# LEDDriver.net
KiCad netlist of a schematic drawn in EAGLE
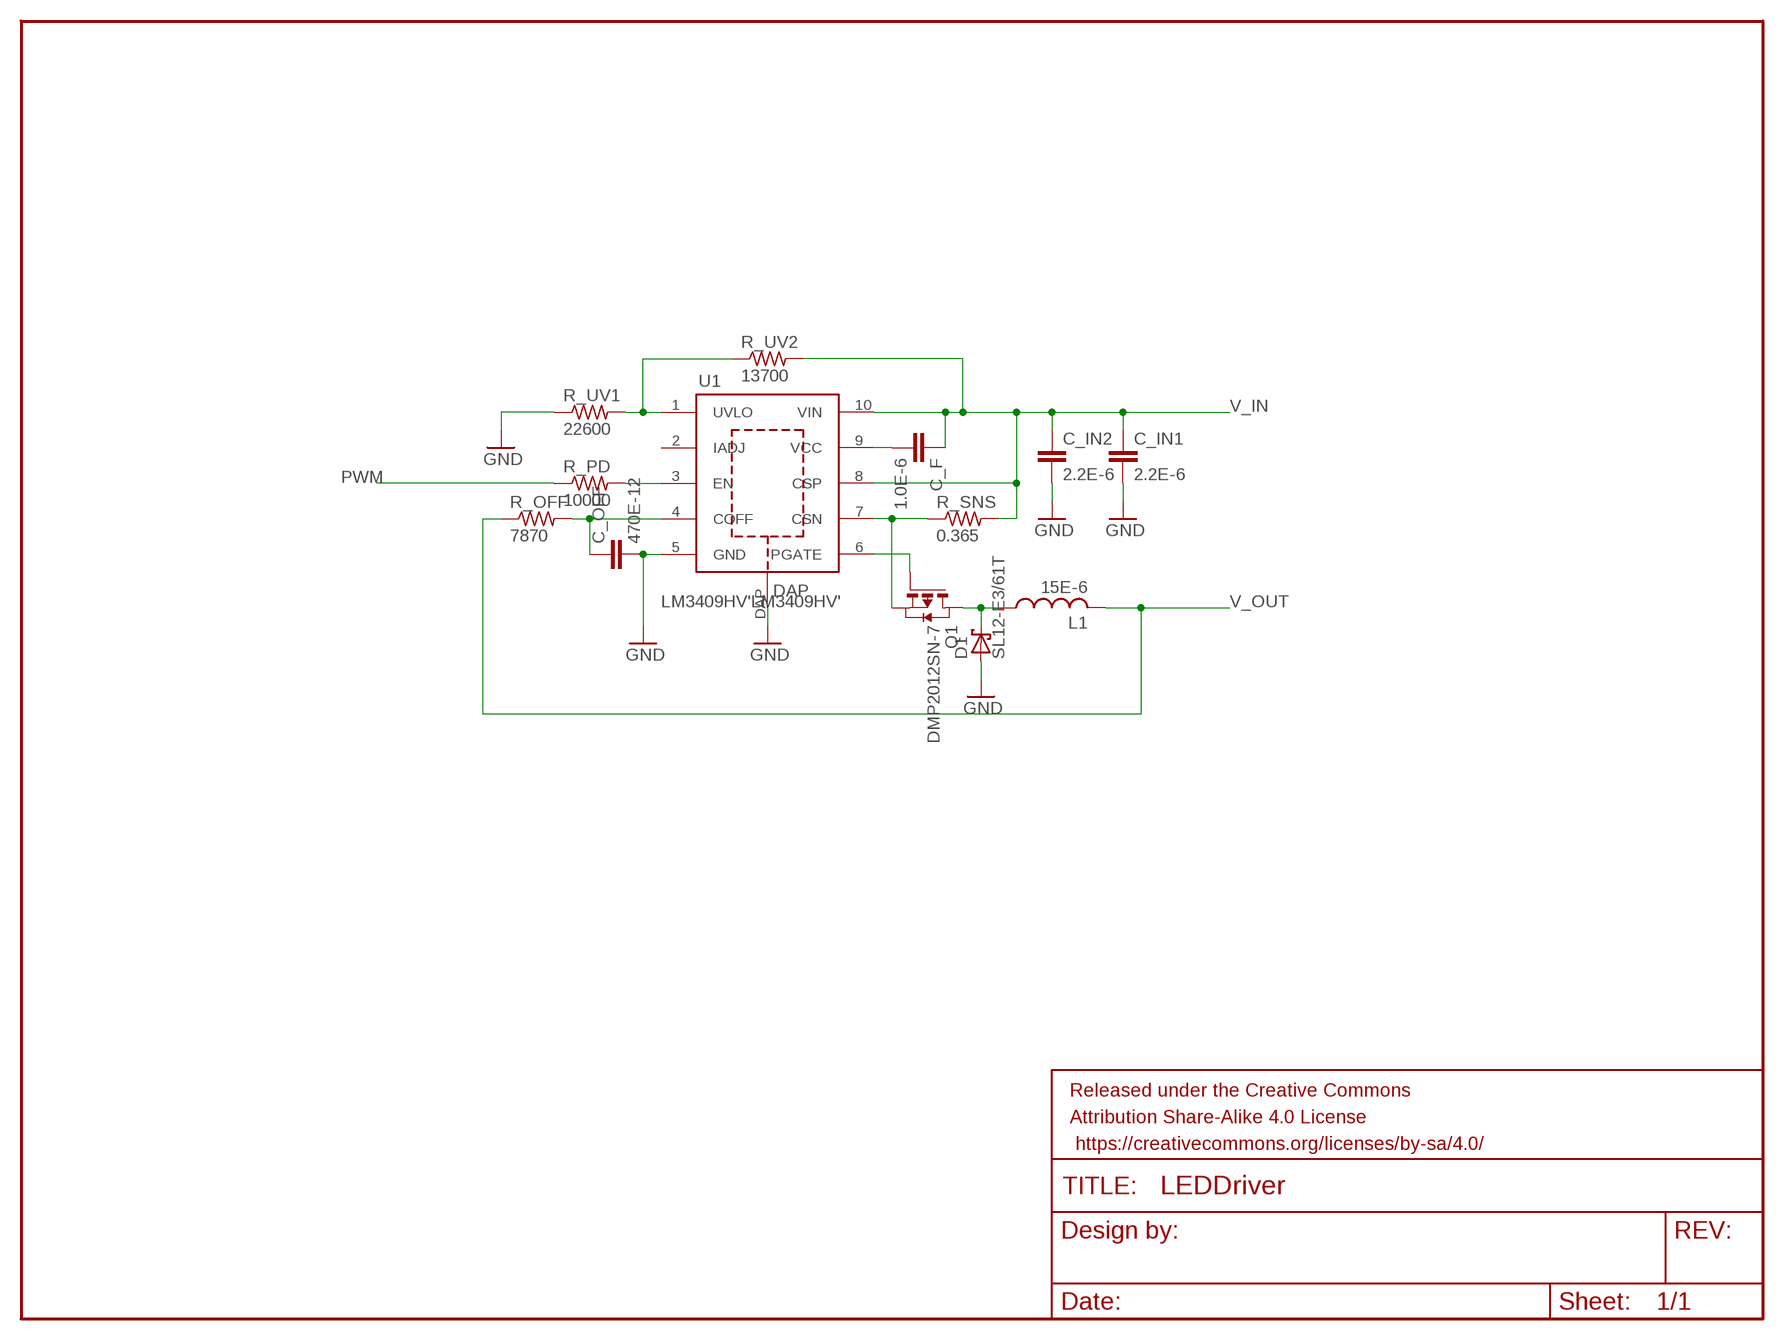
[diagram p0: schematic, sheet 1]

(export (version "E")
  (design (tool "Eeschema 10.0.6"))
  (components
    (comp (ref "C_F")
      (value "1.0E-6")
      (footprint "eagle-import:C0603")
      (libsource (lib "eagle-import") (part "CC0603"))
    )
    (comp (ref "C_IN1")
      (value "2.2E-6")
      (footprint "eagle-import:C0603")
      (libsource (lib "eagle-import") (part "CC0603"))
    )
    (comp (ref "C_IN2")
      (value "2.2E-6")
      (footprint "eagle-import:C0603")
      (libsource (lib "eagle-import") (part "CC0603"))
    )
    (comp (ref "C_OFF")
      (value "470E-12")
      (footprint "eagle-import:C0402")
      (libsource (lib "eagle-import") (part "CC0402"))
    )
    (comp (ref "D1")
      (value "SL12-E3/61T")
      (footprint "eagle-import:SL12-E3_61T")
      (libsource (lib "eagle-import") (part "SL12-E3/61T"))
    )
    (comp (ref "FRAME1")
      (value "FRAME-LETTER")
      (footprint "eagle-import:CREATIVE_COMMONS")
      (libsource (lib "eagle-import") (part "FRAME-LETTER"))
    )
    (comp (ref "L1")
      (value "15E-6")
      (footprint "eagle-import:SRN8040")
      (libsource (lib "eagle-import") (part "SRN8040"))
    )
    (comp (ref "Q1")
      (value "DMP2012SN-7")
      (footprint "eagle-import:DMP2012SN-7")
      (libsource (lib "eagle-import") (part "DMP2012SN-7"))
    )
    (comp (ref "R_OFF")
      (value "7870")
      (footprint "eagle-import:R0603")
      (libsource (lib "eagle-import") (part "R-US_R0603"))
    )
    (comp (ref "R_PD")
      (value "10000")
      (footprint "eagle-import:R0603")
      (libsource (lib "eagle-import") (part "R-US_R0603"))
    )
    (comp (ref "R_SNS")
      (value "0.365")
      (footprint "eagle-import:R2512")
      (libsource (lib "eagle-import") (part "R-US_R2512"))
    )
    (comp (ref "R_UV1")
      (value "22600")
      (footprint "eagle-import:R0603")
      (libsource (lib "eagle-import") (part "R-US_R0603"))
    )
    (comp (ref "R_UV2")
      (value "13700")
      (footprint "eagle-import:R0603")
      (libsource (lib "eagle-import") (part "R-US_R0603"))
    )
    (comp (ref "U1")
      (value "LM3409HV'LM3409HV'")
      (footprint "eagle-import:VSSOP-10")
      (libsource (lib "eagle-import") (part "LM3409HV'LM3409HV'"))
    )
  )
  (nets
    (net (code "1") (name "/PWM") (class "Default")
      (node (ref "R_PD") (pin "1") (pinfunction "1_1") (pintype "passive"))
    )
    (net (code "2") (name "/V_IN") (class "Default")
      (node (ref "C_F") (pin "1") (pinfunction "1_1") (pintype "passive"))
      (node (ref "C_IN1") (pin "1") (pinfunction "1_1") (pintype "passive"))
      (node (ref "C_IN2") (pin "1") (pinfunction "1_1") (pintype "passive"))
      (node (ref "R_SNS") (pin "2") (pinfunction "2_2") (pintype "passive"))
      (node (ref "R_UV2") (pin "2") (pinfunction "2_2") (pintype "passive"))
      (node (ref "U1") (pin "10") (pinfunction "VIN_10") (pintype "bidirectional"))
      (node (ref "U1") (pin "8") (pinfunction "CSP_8") (pintype "bidirectional"))
    )
    (net (code "3") (name "/V_OUT") (class "Default")
      (node (ref "L1") (pin "2") (pinfunction "2_2") (pintype "passive"))
      (node (ref "R_OFF") (pin "1") (pinfunction "1_1") (pintype "passive"))
    )
    (net (code "4") (name "GND") (class "Default")
      (node (ref "C_IN1") (pin "2") (pinfunction "2_2") (pintype "passive"))
      (node (ref "C_IN2") (pin "2") (pinfunction "2_2") (pintype "passive"))
      (node (ref "C_OFF") (pin "2") (pinfunction "2_2") (pintype "passive"))
      (node (ref "D1") (pin "2") (pinfunction "A_2") (pintype "passive"))
      (node (ref "R_UV1") (pin "1") (pinfunction "1_1") (pintype "passive"))
      (node (ref "U1") (pin "5") (pinfunction "GND_5") (pintype "bidirectional"))
      (node (ref "U1") (pin "DAP") (pinfunction "DAP_DAP") (pintype "bidirectional"))
    )
    (net (code "5") (name "Net-(D1-C)") (class "Default")
      (node (ref "D1") (pin "1") (pinfunction "C_1") (pintype "passive"))
      (node (ref "L1") (pin "1") (pinfunction "1_1") (pintype "passive"))
      (node (ref "Q1") (pin "1") (pinfunction "D_1") (pintype "passive"))
    )
    (net (code "6") (name "Net-(Q1-G)") (class "Default")
      (node (ref "Q1") (pin "2") (pinfunction "G_2") (pintype "passive"))
      (node (ref "U1") (pin "6") (pinfunction "PGATE_6") (pintype "bidirectional"))
    )
    (net (code "7") (name "Net-(Q1-S)") (class "Default")
      (node (ref "Q1") (pin "3") (pinfunction "S_3") (pintype "passive"))
      (node (ref "R_SNS") (pin "1") (pinfunction "1_1") (pintype "passive"))
      (node (ref "U1") (pin "7") (pinfunction "CSN_7") (pintype "bidirectional"))
    )
    (net (code "8") (name "Net-(U1-COFF)") (class "Default")
      (node (ref "C_OFF") (pin "1") (pinfunction "1_1") (pintype "passive"))
      (node (ref "R_OFF") (pin "2") (pinfunction "2_2") (pintype "passive"))
      (node (ref "U1") (pin "4") (pinfunction "COFF_4") (pintype "bidirectional"))
    )
    (net (code "9") (name "Net-(U1-EN)") (class "Default")
      (node (ref "R_PD") (pin "2") (pinfunction "2_2") (pintype "passive"))
      (node (ref "U1") (pin "3") (pinfunction "EN_3") (pintype "bidirectional"))
    )
    (net (code "10") (name "Net-(U1-UVLO)") (class "Default")
      (node (ref "R_UV1") (pin "2") (pinfunction "2_2") (pintype "passive"))
      (node (ref "R_UV2") (pin "1") (pinfunction "1_1") (pintype "passive"))
      (node (ref "U1") (pin "1") (pinfunction "UVLO_1") (pintype "bidirectional"))
    )
    (net (code "11") (name "Net-(U1-VCC)") (class "Default")
      (node (ref "C_F") (pin "2") (pinfunction "2_2") (pintype "passive"))
      (node (ref "U1") (pin "9") (pinfunction "VCC_9") (pintype "bidirectional"))
    )
    (net (code "12") (name "unconnected-(U1-IADJ-Pad2)") (class "Default")
      (node (ref "U1") (pin "2") (pinfunction "IADJ_2") (pintype "bidirectional"))
    )
  )
)
